# CAM-M8Q-Breakout_v12.net
KiCad netlist of a schematic drawn in EAGLE
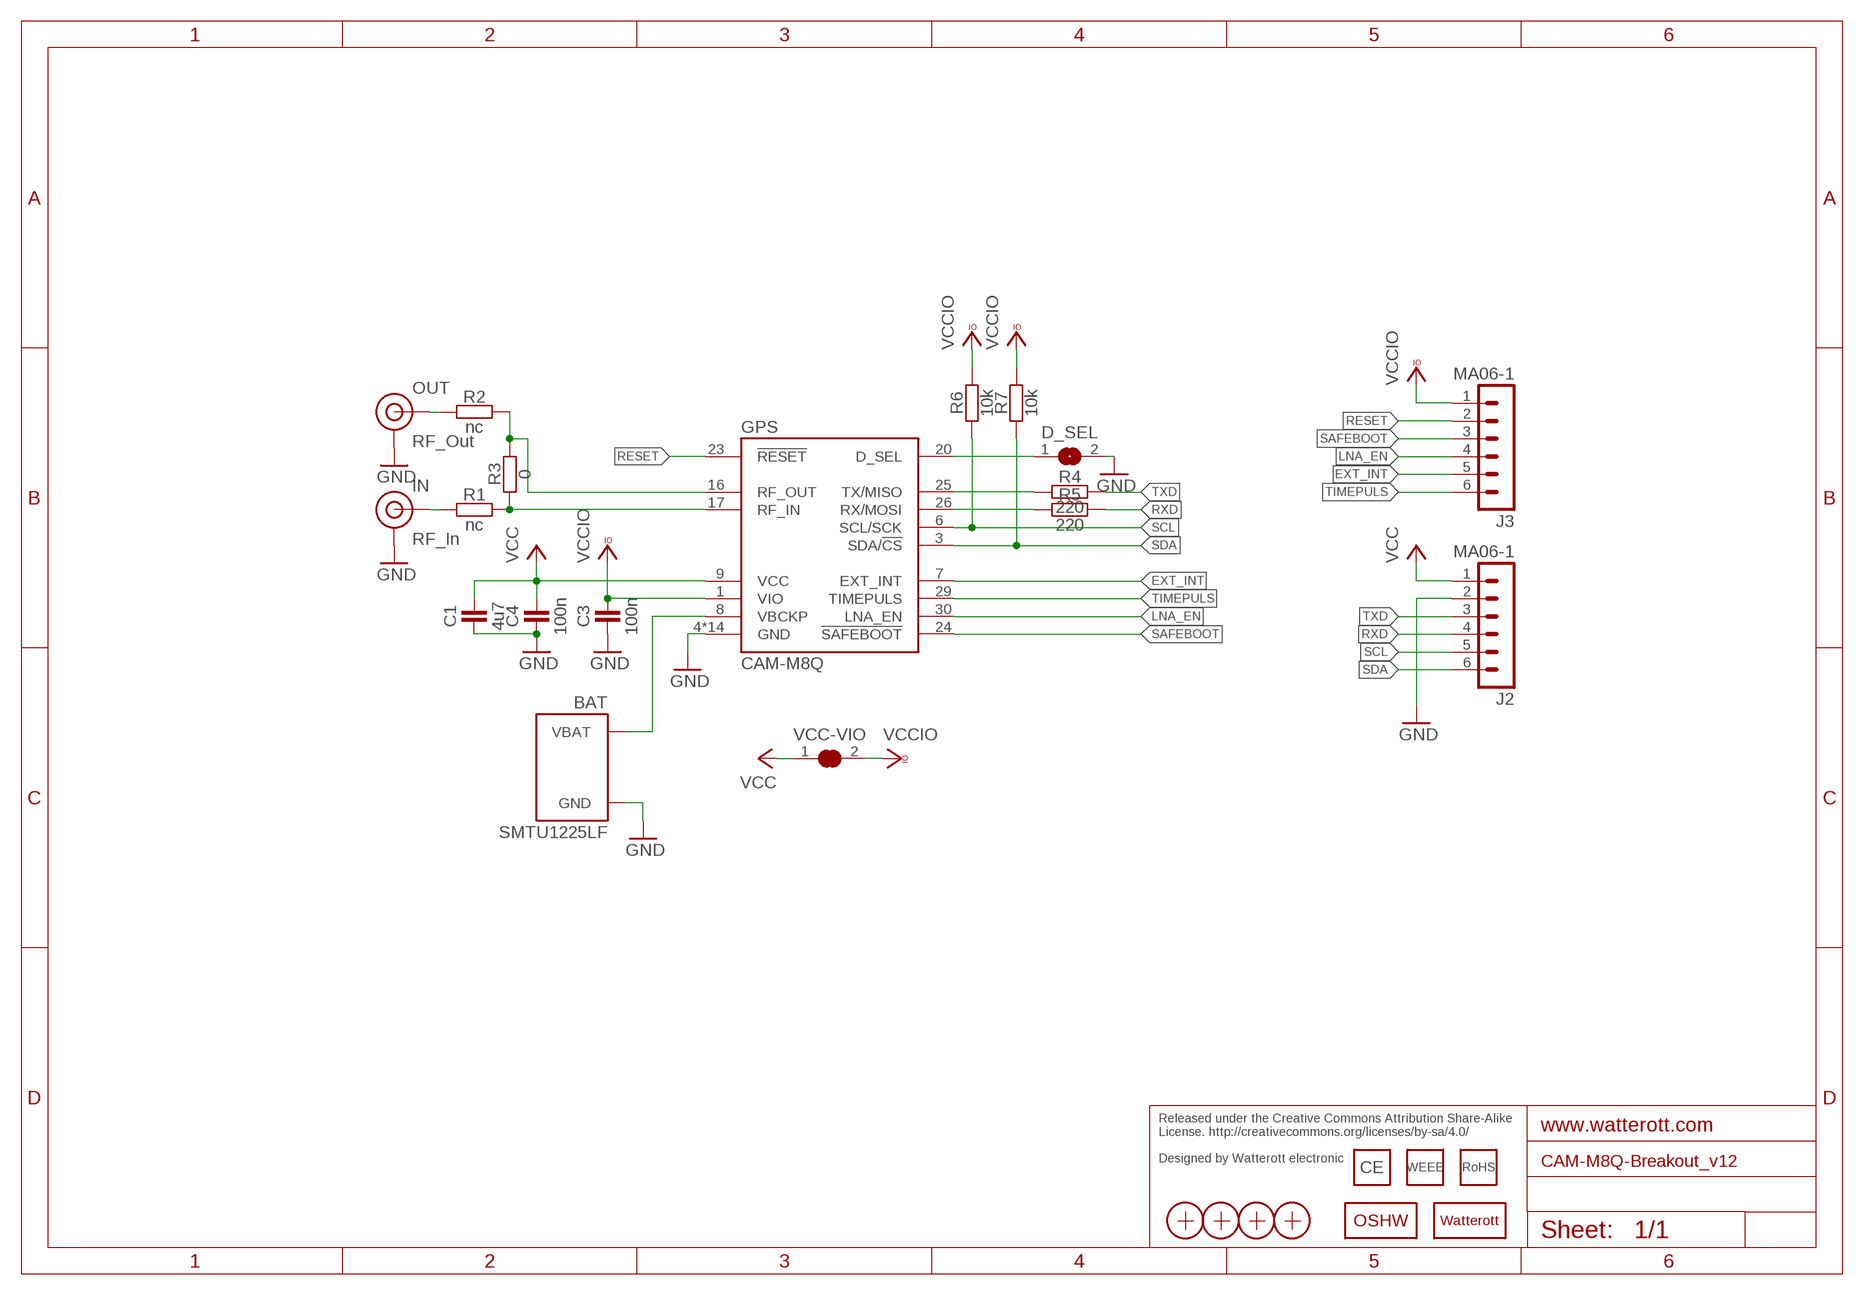
[diagram p0: schematic, sheet 1]

(export (version "E")
  (design (tool "Eeschema 10.0.6"))
  (components
    (comp (ref "BAT")
      (value "SMTU1225LF")
      (footprint "eagle-import:BAT-SMTU1225LF")
      (libsource (lib "eagle-import") (part "BATTERY-SMTU1225LF"))
    )
    (comp (ref "C1")
      (value "4u7")
      (footprint "eagle-import:C0402")
      (libsource (lib "eagle-import") (part "CAPACITOR-0402"))
    )
    (comp (ref "C3")
      (value "100n")
      (footprint "eagle-import:C0402")
      (libsource (lib "eagle-import") (part "CAPACITOR-0402"))
    )
    (comp (ref "C4")
      (value "100n")
      (footprint "eagle-import:C0402")
      (libsource (lib "eagle-import") (part "CAPACITOR-0402"))
    )
    (comp (ref "D_SEL")
      (value "JUMPER2-0603-NC")
      (footprint "eagle-import:JUMPER2-0603_NC")
      (libsource (lib "eagle-import") (part "JUMPER2-0603-NC"))
    )
    (comp (ref "GPS")
      (value "CAM-M8Q")
      (footprint "eagle-import:CAM-M8Q")
      (libsource (lib "eagle-import") (part "CAM-M8Q"))
    )
    (comp (ref "IN")
      (value "RF_In")
      (footprint "eagle-import:U.FL")
      (libsource (lib "eagle-import") (part "U.FL"))
    )
    (comp (ref "J2")
      (value "MA06-1")
      (footprint "eagle-import:MA06-1")
      (libsource (lib "eagle-import") (part "MA06-1"))
    )
    (comp (ref "J3")
      (value "MA06-1")
      (footprint "eagle-import:MA06-1")
      (libsource (lib "eagle-import") (part "MA06-1"))
    )
    (comp (ref "LOGO1")
      (value "LOGO-S_PLACE_M")
      (footprint "eagle-import:SPARK_TPLACE_M")
      (libsource (lib "eagle-import") (part "LOGO-S_PLACE_M"))
    )
    (comp (ref "LOGO2")
      (value "OSHW_LOGOX0070")
      (footprint "eagle-import:OSHW_6X70")
      (libsource (lib "eagle-import") (part "OSHW_LOGOX0070"))
    )
    (comp (ref "LOGO3")
      (value "LOGO_CE-2")
      (footprint "eagle-import:CE_2MM")
      (libsource (lib "eagle-import") (part "LOGO_CE-2"))
    )
    (comp (ref "LOGO4")
      (value "LOGO_WEEE-4")
      (footprint "eagle-import:WEEE_4MM")
      (libsource (lib "eagle-import") (part "LOGO_WEEE-4"))
    )
    (comp (ref "LOGO5")
      (value "LOGO_ROHS-2")
      (footprint "eagle-import:ROHS_2MM")
      (libsource (lib "eagle-import") (part "LOGO_ROHS-2"))
    )
    (comp (ref "OUT")
      (value "RF_Out")
      (footprint "eagle-import:U.FL")
      (libsource (lib "eagle-import") (part "U.FL"))
    )
    (comp (ref "R1")
      (value "nc")
      (footprint "eagle-import:C0402")
      (libsource (lib "eagle-import") (part "RESISTOR-0402"))
    )
    (comp (ref "R2")
      (value "nc")
      (footprint "eagle-import:C0402")
      (libsource (lib "eagle-import") (part "RESISTOR-0402"))
    )
    (comp (ref "R3")
      (value "0")
      (footprint "eagle-import:C0402")
      (libsource (lib "eagle-import") (part "RESISTOR-0402"))
    )
    (comp (ref "R4")
      (value "220")
      (footprint "eagle-import:C0402")
      (libsource (lib "eagle-import") (part "RESISTOR-0402"))
    )
    (comp (ref "R5")
      (value "220")
      (footprint "eagle-import:C0402")
      (libsource (lib "eagle-import") (part "RESISTOR-0402"))
    )
    (comp (ref "R6")
      (value "10k")
      (footprint "eagle-import:C0402")
      (libsource (lib "eagle-import") (part "RESISTOR-0402"))
    )
    (comp (ref "R7")
      (value "10k")
      (footprint "eagle-import:C0402")
      (libsource (lib "eagle-import") (part "RESISTOR-0402"))
    )
    (comp (ref "VCC-VIO")
      (value "JUMPER2-0603-NC")
      (footprint "eagle-import:JUMPER2-0603_NC")
      (libsource (lib "eagle-import") (part "JUMPER2-0603-NC"))
    )
    (comp (ref "X1")
      (value "PASSER-07")
      (footprint "eagle-import:PASSER_07MM")
      (libsource (lib "eagle-import") (part "PASSER-07"))
    )
    (comp (ref "X2")
      (value "PASSER-07")
      (footprint "eagle-import:PASSER_07MM")
      (libsource (lib "eagle-import") (part "PASSER-07"))
    )
    (comp (ref "X3")
      (value "PASSER-07")
      (footprint "eagle-import:PASSER_07MM")
      (libsource (lib "eagle-import") (part "PASSER-07"))
    )
    (comp (ref "X4")
      (value "PASSER-07")
      (footprint "eagle-import:PASSER_07MM")
      (libsource (lib "eagle-import") (part "PASSER-07"))
    )
  )
  (nets
    (net (code "1") (name "EXT_INT") (class "Default")
      (node (ref "GPS") (pin "7") (pinfunction "EXT_INT_7") (pintype "bidirectional"))
      (node (ref "J3") (pin "5") (pinfunction "5_5") (pintype "passive"))
    )
    (net (code "2") (name "GND") (class "Default")
      (node (ref "BAT") (pin "-") (pinfunction "GND_-") (pintype "power_in"))
      (node (ref "C1") (pin "1") (pinfunction "1_1") (pintype "passive"))
      (node (ref "C3") (pin "1") (pinfunction "1_1") (pintype "passive"))
      (node (ref "C4") (pin "1") (pinfunction "1_1") (pintype "passive"))
      (node (ref "D_SEL") (pin "2") (pinfunction "2_2") (pintype "passive"))
      (node (ref "GPS") (pin "10") (pinfunction "GND_10") (pintype "power_in"))
      (node (ref "GPS") (pin "11") (pinfunction "GND_11") (pintype "power_in"))
      (node (ref "GPS") (pin "12") (pinfunction "GND_12") (pintype "power_in"))
      (node (ref "GPS") (pin "13") (pinfunction "GND_13") (pintype "power_in"))
      (node (ref "GPS") (pin "14") (pinfunction "GND_14") (pintype "power_in"))
      (node (ref "GPS") (pin "15") (pinfunction "GND_15") (pintype "power_in"))
      (node (ref "GPS") (pin "18") (pinfunction "GND_18") (pintype "power_in"))
      (node (ref "GPS") (pin "19") (pinfunction "GND_19") (pintype "power_in"))
      (node (ref "GPS") (pin "21") (pinfunction "GND_21") (pintype "power_in"))
      (node (ref "GPS") (pin "22") (pinfunction "GND_22") (pintype "power_in"))
      (node (ref "GPS") (pin "27") (pinfunction "GND_27") (pintype "power_in"))
      (node (ref "GPS") (pin "31") (pinfunction "GND_31") (pintype "power_in"))
      (node (ref "GPS") (pin "4") (pinfunction "GND_4") (pintype "power_in"))
      (node (ref "GPS") (pin "5") (pinfunction "GND_5") (pintype "power_in"))
      (node (ref "IN") (pin "1") (pinfunction "GND_1") (pintype "bidirectional"))
      (node (ref "IN") (pin "2") (pinfunction "GND_2") (pintype "bidirectional"))
      (node (ref "J2") (pin "2") (pinfunction "2_2") (pintype "passive"))
      (node (ref "OUT") (pin "1") (pinfunction "GND_1") (pintype "bidirectional"))
      (node (ref "OUT") (pin "2") (pinfunction "GND_2") (pintype "bidirectional"))
    )
    (net (code "3") (name "LNA_EN") (class "Default")
      (node (ref "GPS") (pin "30") (pinfunction "LNA_EN_30") (pintype "bidirectional"))
      (node (ref "J3") (pin "4") (pinfunction "4_4") (pintype "passive"))
    )
    (net (code "4") (name "Net-(BAT-VBAT)") (class "Default")
      (node (ref "BAT") (pin "+") (pinfunction "VBAT_+") (pintype "power_in"))
      (node (ref "GPS") (pin "8") (pinfunction "VBCKP_8") (pintype "power_in"))
    )
    (net (code "5") (name "Net-(GPS-D_SEL)") (class "Default")
      (node (ref "D_SEL") (pin "1") (pinfunction "1_1") (pintype "passive"))
      (node (ref "GPS") (pin "20") (pinfunction "D_SEL_20") (pintype "bidirectional"))
    )
    (net (code "6") (name "Net-(GPS-RF_IN)") (class "Default")
      (node (ref "GPS") (pin "17") (pinfunction "RF_IN_17") (pintype "input"))
      (node (ref "R1") (pin "2") (pinfunction "2_2") (pintype "passive"))
      (node (ref "R3") (pin "1") (pinfunction "1_1") (pintype "passive"))
    )
    (net (code "7") (name "Net-(GPS-RF_OUT)") (class "Default")
      (node (ref "GPS") (pin "16") (pinfunction "RF_OUT_16") (pintype "output"))
      (node (ref "R2") (pin "2") (pinfunction "2_2") (pintype "passive"))
      (node (ref "R3") (pin "2") (pinfunction "2_2") (pintype "passive"))
    )
    (net (code "8") (name "Net-(GPS-RX{slash}MOSI)") (class "Default")
      (node (ref "GPS") (pin "26") (pinfunction "RX/MOSI_26") (pintype "input"))
      (node (ref "R5") (pin "1") (pinfunction "1_1") (pintype "passive"))
    )
    (net (code "9") (name "Net-(GPS-TX{slash}MISO)") (class "Default")
      (node (ref "GPS") (pin "25") (pinfunction "TX/MISO_25") (pintype "output"))
      (node (ref "R4") (pin "1") (pinfunction "1_1") (pintype "passive"))
    )
    (net (code "10") (name "Net-(IN-SIGNAL)") (class "Default")
      (node (ref "IN") (pin "FEED") (pinfunction "SIGNAL_FEED") (pintype "bidirectional"))
      (node (ref "R1") (pin "1") (pinfunction "1_1") (pintype "passive"))
    )
    (net (code "11") (name "Net-(OUT-SIGNAL)") (class "Default")
      (node (ref "OUT") (pin "FEED") (pinfunction "SIGNAL_FEED") (pintype "bidirectional"))
      (node (ref "R2") (pin "1") (pinfunction "1_1") (pintype "passive"))
    )
    (net (code "12") (name "RESET") (class "Default")
      (node (ref "GPS") (pin "23") (pinfunction "~{RESET}_23") (pintype "input"))
      (node (ref "J3") (pin "2") (pinfunction "2_2") (pintype "passive"))
    )
    (net (code "13") (name "RXD") (class "Default")
      (node (ref "J2") (pin "4") (pinfunction "4_4") (pintype "passive"))
      (node (ref "R5") (pin "2") (pinfunction "2_2") (pintype "passive"))
    )
    (net (code "14") (name "SAFEBOOT") (class "Default")
      (node (ref "GPS") (pin "24") (pinfunction "~{SAFEBOOT}_24") (pintype "bidirectional"))
      (node (ref "J3") (pin "3") (pinfunction "3_3") (pintype "passive"))
    )
    (net (code "15") (name "SCL") (class "Default")
      (node (ref "GPS") (pin "6") (pinfunction "SCL/SCK_6") (pintype "bidirectional"))
      (node (ref "J2") (pin "5") (pinfunction "5_5") (pintype "passive"))
      (node (ref "R6") (pin "1") (pinfunction "1_1") (pintype "passive"))
    )
    (net (code "16") (name "SDA") (class "Default")
      (node (ref "GPS") (pin "3") (pinfunction "SDA/~{CS}_3") (pintype "bidirectional"))
      (node (ref "J2") (pin "6") (pinfunction "6_6") (pintype "passive"))
      (node (ref "R7") (pin "1") (pinfunction "1_1") (pintype "passive"))
    )
    (net (code "17") (name "TIMEPULS") (class "Default")
      (node (ref "GPS") (pin "29") (pinfunction "TIMEPULS_29") (pintype "output"))
      (node (ref "J3") (pin "6") (pinfunction "6_6") (pintype "passive"))
    )
    (net (code "18") (name "TXD") (class "Default")
      (node (ref "J2") (pin "3") (pinfunction "3_3") (pintype "passive"))
      (node (ref "R4") (pin "2") (pinfunction "2_2") (pintype "passive"))
    )
    (net (code "19") (name "VCC") (class "Default")
      (node (ref "C1") (pin "2") (pinfunction "2_2") (pintype "passive"))
      (node (ref "C4") (pin "2") (pinfunction "2_2") (pintype "passive"))
      (node (ref "GPS") (pin "9") (pinfunction "VCC_9") (pintype "power_in"))
      (node (ref "J2") (pin "1") (pinfunction "1_1") (pintype "passive"))
      (node (ref "VCC-VIO") (pin "1") (pinfunction "1_1") (pintype "passive"))
    )
    (net (code "20") (name "VCCIO") (class "Default")
      (node (ref "C3") (pin "2") (pinfunction "2_2") (pintype "passive"))
      (node (ref "GPS") (pin "1") (pinfunction "VIO_1") (pintype "power_in"))
      (node (ref "J3") (pin "1") (pinfunction "1_1") (pintype "passive"))
      (node (ref "R6") (pin "2") (pinfunction "2_2") (pintype "passive"))
      (node (ref "R7") (pin "2") (pinfunction "2_2") (pintype "passive"))
      (node (ref "VCC-VIO") (pin "2") (pinfunction "2_2") (pintype "passive"))
    )
  )
)
